# MotorCell_noPow.net
KiCad netlist of a schematic drawn in Altium Designer
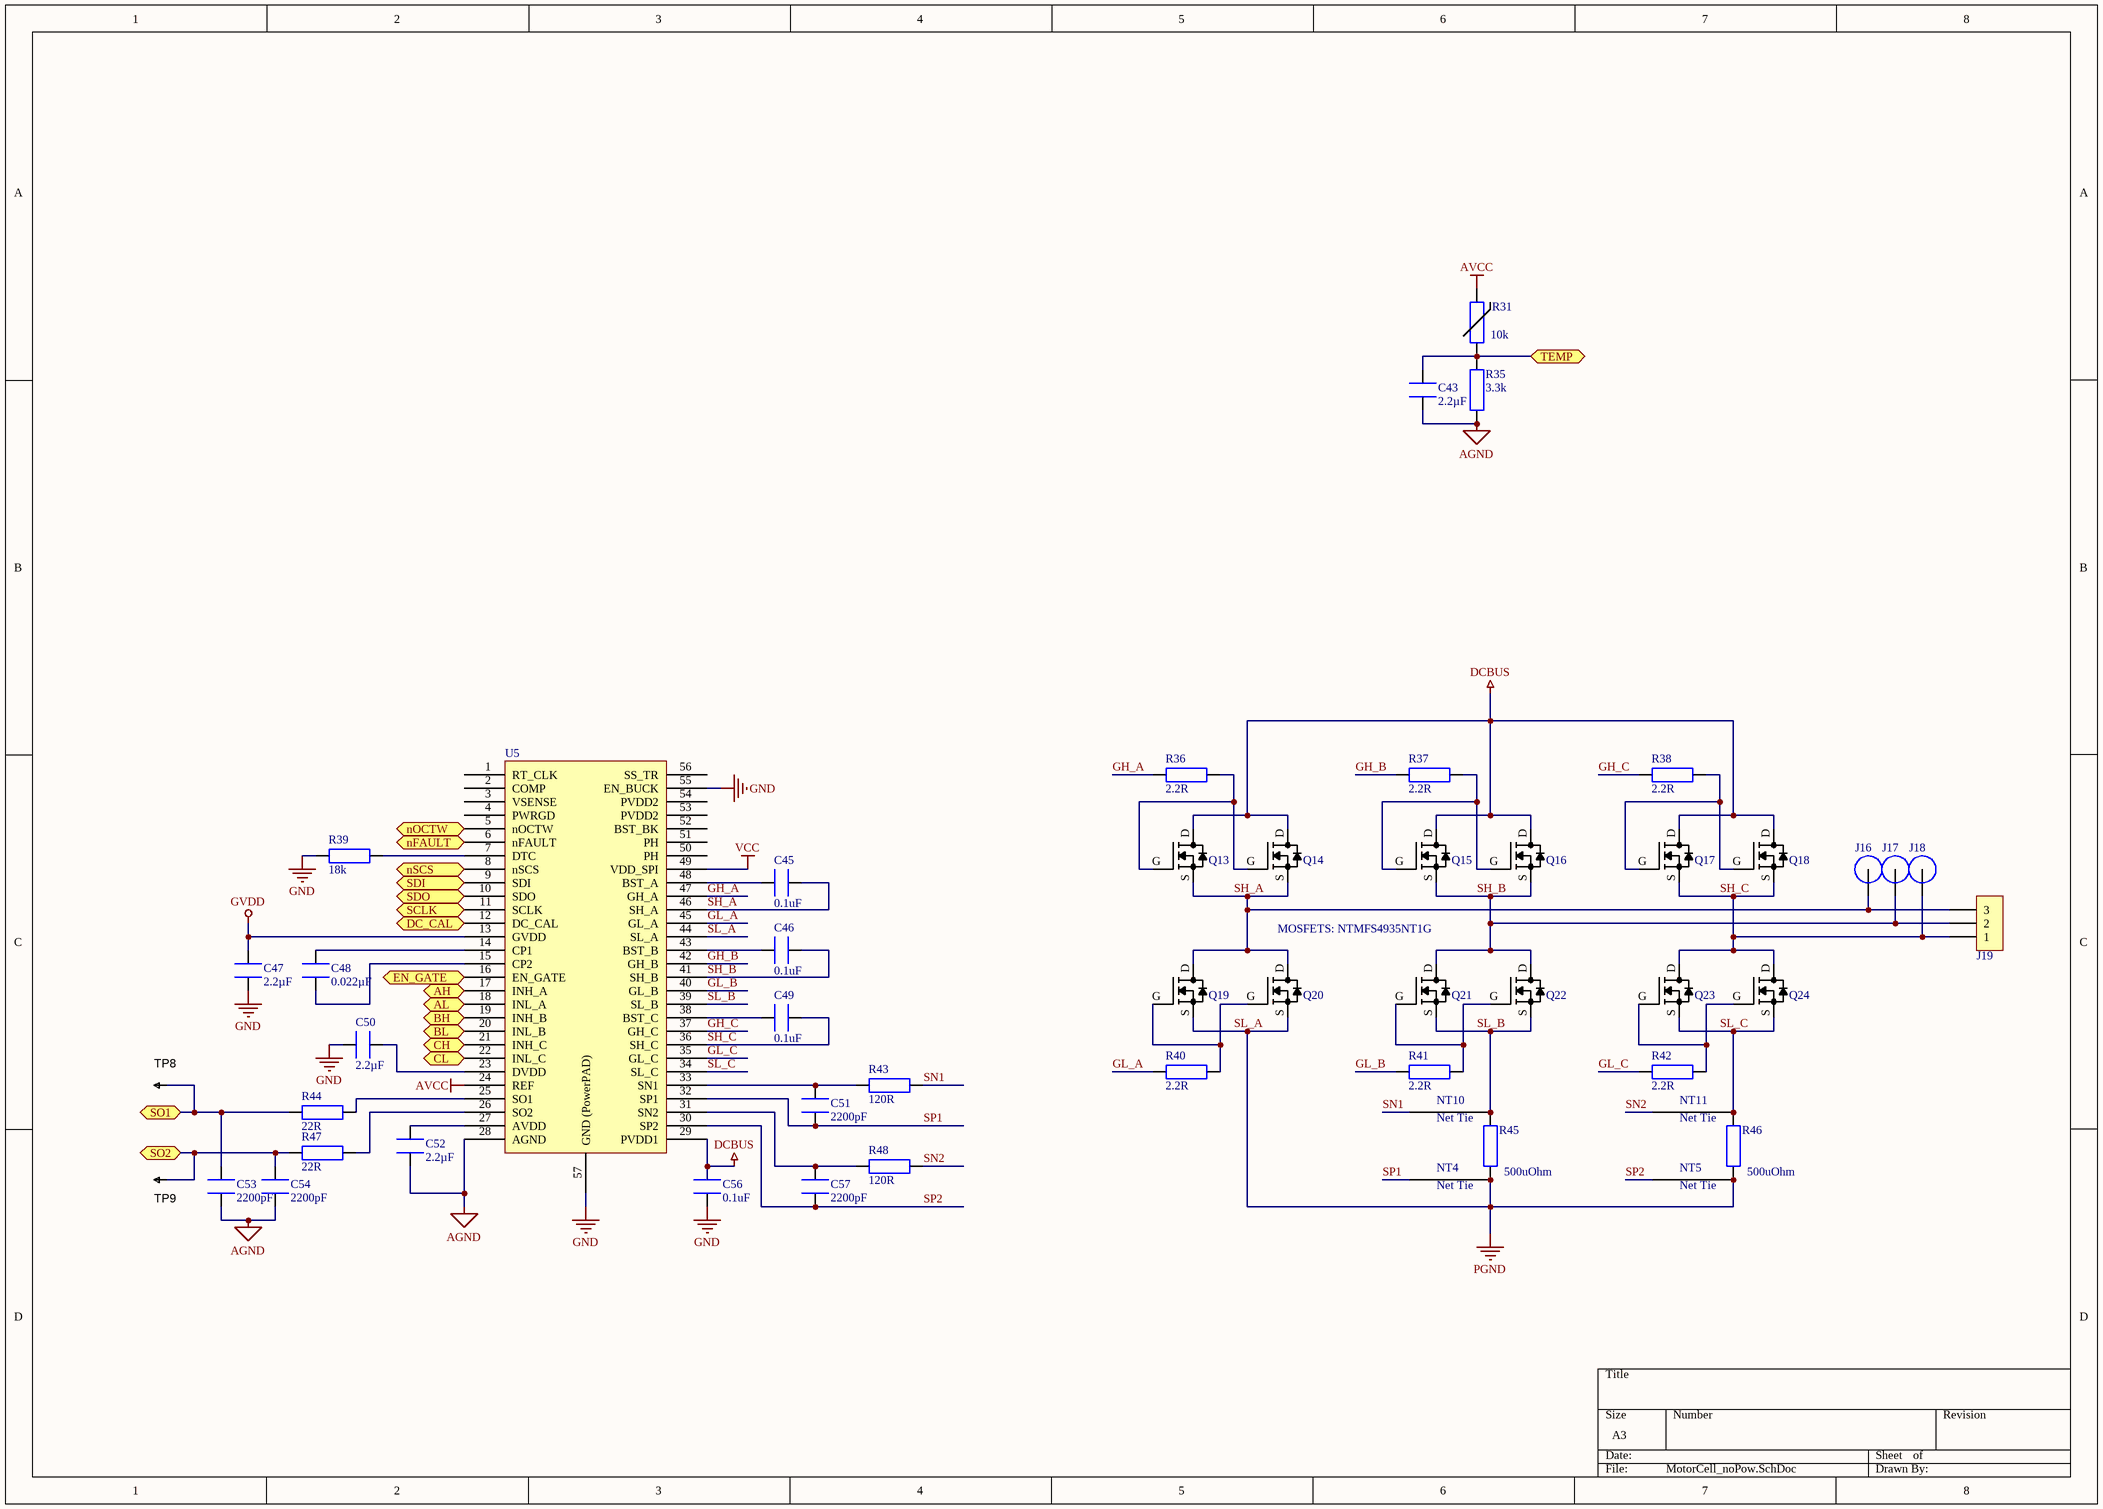
[diagram p0: MotorCell_noPow.SchDoc]

(export (version "E")
  (design (tool "Eeschema 10.0.6"))
  (components
    (comp (ref "C43")
      (value "2.2µF")
      (footprint "CAPC1608X09L")
      (description "CAP CER 2.2UF 16V X5R 0603")
      (fields
        (field (name "MANUFACTURER") "Murata Electronics North America")
        (field (name "MANUFACTURER PART NUMBER") "GRM188R61C225KE15D")
      )
      (libsource (lib "CustomComponents") (part "GRM188R61C225KE15D"))
    )
    (comp (ref "C45")
      (value "0.1uF")
      (footprint "CAPC1608X09L")
      (description "CAP CER 0.1UF 50V X7R 0603")
      (fields
        (field (name "MANUFACTURER") "Murata Electronics North America")
        (field (name "MANUFACTURER PART NUMBER") "GRM188R71H104KA93D")
      )
      (libsource (lib "CustomComponents") (part "GRM188R71H104KA93D"))
    )
    (comp (ref "C46")
      (value "0.1uF")
      (footprint "CAPC1608X09L")
      (description "CAP CER 0.1UF 50V X7R 0603")
      (fields
        (field (name "MANUFACTURER") "Murata Electronics North America")
        (field (name "MANUFACTURER PART NUMBER") "GRM188R71H104KA93D")
      )
      (libsource (lib "CustomComponents") (part "GRM188R71H104KA93D"))
    )
    (comp (ref "C47")
      (value "2.2µF")
      (footprint "CAPC1608X09L")
      (description "CAP CER 2.2UF 16V X5R 0603")
      (fields
        (field (name "MANUFACTURER") "Murata Electronics North America")
        (field (name "MANUFACTURER PART NUMBER") "GRM188R61C225KE15D")
      )
      (libsource (lib "CustomComponents") (part "GRM188R61C225KE15D"))
    )
    (comp (ref "C48")
      (value "0.022µF")
      (footprint "CAPC1608X09L")
      (description "CAP CER 0.022UF 50V X7R 0603")
      (fields
        (field (name "MANUFACTURER") "Murata Electronics North America")
        (field (name "MANUFACTURER PART NUMBER") "GRM188R71H223KA01D")
      )
      (libsource (lib "CustomComponents") (part "GRM188R71H223KA01D"))
    )
    (comp (ref "C49")
      (value "0.1uF")
      (footprint "CAPC1608X09L")
      (description "CAP CER 0.1UF 50V X7R 0603")
      (fields
        (field (name "MANUFACTURER") "Murata Electronics North America")
        (field (name "MANUFACTURER PART NUMBER") "GRM188R71H104KA93D")
      )
      (libsource (lib "CustomComponents") (part "GRM188R71H104KA93D"))
    )
    (comp (ref "C50")
      (value "2.2µF")
      (footprint "CAPC1608X09L")
      (description "CAP CER 2.2UF 16V X5R 0603")
      (fields
        (field (name "MANUFACTURER") "Murata Electronics North America")
        (field (name "MANUFACTURER PART NUMBER") "GRM188R61C225KE15D")
      )
      (libsource (lib "CustomComponents") (part "GRM188R61C225KE15D"))
    )
    (comp (ref "C51")
      (value "2200pF")
      (footprint "CAPC1608X09L")
      (description "CAP CER 2200PF 50V NP0 0603")
      (fields
        (field (name "MANUFACTURER") "Murata Electronics North America")
        (field (name "TOLERANCE") "±5%")
      )
      (libsource (lib "CustomComponents") (part "GRM1885C1H222JA01D"))
    )
    (comp (ref "C52")
      (value "2.2µF")
      (footprint "CAPC1608X09L")
      (description "CAP CER 2.2UF 16V X5R 0603")
      (fields
        (field (name "MANUFACTURER") "Murata Electronics North America")
        (field (name "MANUFACTURER PART NUMBER") "GRM188R61C225KE15D")
      )
      (libsource (lib "CustomComponents") (part "GRM188R61C225KE15D"))
    )
    (comp (ref "C53")
      (value "2200pF")
      (footprint "CAPC1608X09L")
      (description "CAP CER 2200PF 50V NP0 0603")
      (fields
        (field (name "MANUFACTURER") "Murata Electronics North America")
        (field (name "TOLERANCE") "±5%")
      )
      (libsource (lib "CustomComponents") (part "GRM1885C1H222JA01D"))
    )
    (comp (ref "C54")
      (value "2200pF")
      (footprint "CAPC1608X09L")
      (description "CAP CER 2200PF 50V NP0 0603")
      (fields
        (field (name "MANUFACTURER") "Murata Electronics North America")
        (field (name "TOLERANCE") "±5%")
      )
      (libsource (lib "CustomComponents") (part "GRM1885C1H222JA01D"))
    )
    (comp (ref "C56")
      (value "0.1uF")
      (footprint "CAPC1608X09L")
      (description "CAP CER 0.1UF 50V X7R 0603")
      (fields
        (field (name "MANUFACTURER") "Murata Electronics North America")
        (field (name "MANUFACTURER PART NUMBER") "GRM188R71H104KA93D")
      )
      (libsource (lib "CustomComponents") (part "GRM188R71H104KA93D"))
    )
    (comp (ref "C57")
      (value "2200pF")
      (footprint "CAPC1608X09L")
      (description "CAP CER 2200PF 50V NP0 0603")
      (fields
        (field (name "MANUFACTURER") "Murata Electronics North America")
        (field (name "TOLERANCE") "±5%")
      )
      (libsource (lib "CustomComponents") (part "GRM1885C1H222JA01D"))
    )
    (comp (ref "J16")
      (value "~")
      (footprint "M3 Spade Hole")
      (description "M3 Spade Terminal")
      (libsource (lib "CustomComponents") (part "M3 Spade Terminal"))
    )
    (comp (ref "J17")
      (value "~")
      (footprint "M3 Spade Hole")
      (description "M3 Spade Terminal")
      (libsource (lib "CustomComponents") (part "M3 Spade Terminal"))
    )
    (comp (ref "J18")
      (value "~")
      (footprint "M3 Spade Hole")
      (description "M3 Spade Terminal")
      (libsource (lib "CustomComponents") (part "M3 Spade Terminal"))
    )
    (comp (ref "J19")
      (value "1704936")
      (footprint "1704936")
      (description "CONN TERM BLOCK 3POS 7.62MM")
      (fields (field (name "MANUFACTURER") "Phoenix Contact") (field (name "VOLTAGE") "300V"))
      (libsource (lib "CustomComponents") (part "1704936"))
    )
    (comp (ref "NT4")
      (value "0.25mm")
      (footprint "NetTie_0.25mm")
      (libsource (lib "CustomComponents") (part "NetTie_0.25mm"))
    )
    (comp (ref "NT5")
      (value "0.25mm")
      (footprint "NetTie_0.25mm")
      (libsource (lib "CustomComponents") (part "NetTie_0.25mm"))
    )
    (comp (ref "NT10")
      (value "0.25mm")
      (footprint "NetTie_0.25mm")
      (libsource (lib "CustomComponents") (part "NetTie_0.25mm"))
    )
    (comp (ref "NT11")
      (value "0.25mm")
      (footprint "NetTie_0.25mm")
      (libsource (lib "CustomComponents") (part "NetTie_0.25mm"))
    )
    (comp (ref "Q13")
      (value "~")
      (footprint "SO8FL")
      (description "MOSFET N-CH 30V 13A SO8FL")
      (fields
        (field (name "MANUFACTURER") "ON Semiconductor")
        (field (name "MANUFACTURER PART NUMBER") "NTMFS4935NT1G")
      )
      (libsource (lib "CustomComponents") (part "NTMFS4935NT1G"))
    )
    (comp (ref "Q14")
      (value "FILL_FOOTPRINT")
      (footprint "SO8FL_FILL")
      (description "MOSFET N-CH 30V 13A SO8FL")
      (fields
        (field (name "MANUFACTURER") "ON Semiconductor")
        (field (name "MANUFACTURER PART NUMBER") "NTMFS4935NT1G")
      )
      (libsource (lib "CustomComponents") (part "NTMFS4935NT1G"))
    )
    (comp (ref "Q15")
      (value "~")
      (footprint "SO8FL")
      (description "MOSFET N-CH 30V 13A SO8FL")
      (fields
        (field (name "MANUFACTURER") "ON Semiconductor")
        (field (name "MANUFACTURER PART NUMBER") "NTMFS4935NT1G")
      )
      (libsource (lib "CustomComponents") (part "NTMFS4935NT1G"))
    )
    (comp (ref "Q16")
      (value "FILL_FOOTPRINT")
      (footprint "SO8FL_FILL")
      (description "MOSFET N-CH 30V 13A SO8FL")
      (fields
        (field (name "MANUFACTURER") "ON Semiconductor")
        (field (name "MANUFACTURER PART NUMBER") "NTMFS4935NT1G")
      )
      (libsource (lib "CustomComponents") (part "NTMFS4935NT1G"))
    )
    (comp (ref "Q17")
      (value "~")
      (footprint "SO8FL")
      (description "MOSFET N-CH 30V 13A SO8FL")
      (fields
        (field (name "MANUFACTURER") "ON Semiconductor")
        (field (name "MANUFACTURER PART NUMBER") "NTMFS4935NT1G")
      )
      (libsource (lib "CustomComponents") (part "NTMFS4935NT1G"))
    )
    (comp (ref "Q18")
      (value "FILL_FOOTPRINT")
      (footprint "SO8FL_FILL")
      (description "MOSFET N-CH 30V 13A SO8FL")
      (fields
        (field (name "MANUFACTURER") "ON Semiconductor")
        (field (name "MANUFACTURER PART NUMBER") "NTMFS4935NT1G")
      )
      (libsource (lib "CustomComponents") (part "NTMFS4935NT1G"))
    )
    (comp (ref "Q19")
      (value "~")
      (footprint "SO8FL")
      (description "MOSFET N-CH 30V 13A SO8FL")
      (fields
        (field (name "MANUFACTURER") "ON Semiconductor")
        (field (name "MANUFACTURER PART NUMBER") "NTMFS4935NT1G")
      )
      (libsource (lib "CustomComponents") (part "NTMFS4935NT1G"))
    )
    (comp (ref "Q20")
      (value "~")
      (footprint "SO8FL")
      (description "MOSFET N-CH 30V 13A SO8FL")
      (fields
        (field (name "MANUFACTURER") "ON Semiconductor")
        (field (name "MANUFACTURER PART NUMBER") "NTMFS4935NT1G")
      )
      (libsource (lib "CustomComponents") (part "NTMFS4935NT1G"))
    )
    (comp (ref "Q21")
      (value "~")
      (footprint "SO8FL")
      (description "MOSFET N-CH 30V 13A SO8FL")
      (fields
        (field (name "MANUFACTURER") "ON Semiconductor")
        (field (name "MANUFACTURER PART NUMBER") "NTMFS4935NT1G")
      )
      (libsource (lib "CustomComponents") (part "NTMFS4935NT1G"))
    )
    (comp (ref "Q22")
      (value "~")
      (footprint "SO8FL")
      (description "MOSFET N-CH 30V 13A SO8FL")
      (fields
        (field (name "MANUFACTURER") "ON Semiconductor")
        (field (name "MANUFACTURER PART NUMBER") "NTMFS4935NT1G")
      )
      (libsource (lib "CustomComponents") (part "NTMFS4935NT1G"))
    )
    (comp (ref "Q23")
      (value "~")
      (footprint "SO8FL")
      (description "MOSFET N-CH 30V 13A SO8FL")
      (fields
        (field (name "MANUFACTURER") "ON Semiconductor")
        (field (name "MANUFACTURER PART NUMBER") "NTMFS4935NT1G")
      )
      (libsource (lib "CustomComponents") (part "NTMFS4935NT1G"))
    )
    (comp (ref "Q24")
      (value "~")
      (footprint "SO8FL")
      (description "MOSFET N-CH 30V 13A SO8FL")
      (fields
        (field (name "MANUFACTURER") "ON Semiconductor")
        (field (name "MANUFACTURER PART NUMBER") "NTMFS4935NT1G")
      )
      (libsource (lib "CustomComponents") (part "NTMFS4935NT1G"))
    )
    (comp (ref "R31")
      (value "10k")
      (footprint "RESC1005X40N")
      (description "THERMISTOR 10K OHM NTC 0402 SMD")
      (libsource (lib "CustomComponents") (part "NCP15XH103F03RC"))
    )
    (comp (ref "R35")
      (value "3.3k")
      (footprint "RESC1608X55N")
      (description "RES SMD 3.3K OHM 1% 1/10W 0603")
      (fields
        (field (name "MANUFACTURER") "Yageo")
        (field (name "MANUFACTURER PART NUMBER") "RC0603FR-073K3L")
      )
      (libsource (lib "CustomComponents") (part "RC0603FR-073K3L"))
    )
    (comp (ref "R36")
      (value "2.2R")
      (footprint "RESC1608X55N")
      (description "RES SMD 2.2 OHM 1% 1/10W 0603")
      (fields
        (field (name "MANUFACTURER") "Yageo")
        (field (name "MANUFACTURER PART NUMBER") "RC0603FR-072R2L")
      )
      (libsource (lib "CustomComponents") (part "RC0603FR-072R2L"))
    )
    (comp (ref "R37")
      (value "2.2R")
      (footprint "RESC1608X55N")
      (description "RES SMD 2.2 OHM 1% 1/10W 0603")
      (fields
        (field (name "MANUFACTURER") "Yageo")
        (field (name "MANUFACTURER PART NUMBER") "RC0603FR-072R2L")
      )
      (libsource (lib "CustomComponents") (part "RC0603FR-072R2L"))
    )
    (comp (ref "R38")
      (value "2.2R")
      (footprint "RESC1608X55N")
      (description "RES SMD 2.2 OHM 1% 1/10W 0603")
      (fields
        (field (name "MANUFACTURER") "Yageo")
        (field (name "MANUFACTURER PART NUMBER") "RC0603FR-072R2L")
      )
      (libsource (lib "CustomComponents") (part "RC0603FR-072R2L"))
    )
    (comp (ref "R39")
      (value "18k")
      (footprint "RESC1608X55N")
      (description "RES SMD 18K OHM 1% 1/10W 0603")
      (fields
        (field (name "MANUFACTURER") "Yageo")
        (field (name "MANUFACTURER PART NUMBER") "RC0603FR-0718KL")
      )
      (libsource (lib "CustomComponents") (part "RC0603FR-0718KL"))
    )
    (comp (ref "R40")
      (value "2.2R")
      (footprint "RESC1608X55N")
      (description "RES SMD 2.2 OHM 1% 1/10W 0603")
      (fields
        (field (name "MANUFACTURER") "Yageo")
        (field (name "MANUFACTURER PART NUMBER") "RC0603FR-072R2L")
      )
      (libsource (lib "CustomComponents") (part "RC0603FR-072R2L"))
    )
    (comp (ref "R41")
      (value "2.2R")
      (footprint "RESC1608X55N")
      (description "RES SMD 2.2 OHM 1% 1/10W 0603")
      (fields
        (field (name "MANUFACTURER") "Yageo")
        (field (name "MANUFACTURER PART NUMBER") "RC0603FR-072R2L")
      )
      (libsource (lib "CustomComponents") (part "RC0603FR-072R2L"))
    )
    (comp (ref "R42")
      (value "2.2R")
      (footprint "RESC1608X55N")
      (description "RES SMD 2.2 OHM 1% 1/10W 0603")
      (fields
        (field (name "MANUFACTURER") "Yageo")
        (field (name "MANUFACTURER PART NUMBER") "RC0603FR-072R2L")
      )
      (libsource (lib "CustomComponents") (part "RC0603FR-072R2L"))
    )
    (comp (ref "R43")
      (value "120R")
      (footprint "RESC1608X55N")
      (description "RES SMD 120 OHM 1% 1/10W 0603")
      (fields
        (field (name "MANUFACTURER") "Yageo")
        (field (name "MANUFACTURER PART NUMBER") "RC0603FR-07120RL")
      )
      (libsource (lib "CustomComponents") (part "RC0603FR-07120RL"))
    )
    (comp (ref "R44")
      (value "22R")
      (footprint "RESC1608X55N")
      (description "RES SMD 22 OHM 1% 1/10W 0603")
      (fields
        (field (name "MANUFACTURER") "Yageo")
        (field (name "MANUFACTURER PART NUMBER") "RC0603FR-0722RL")
      )
      (libsource (lib "CustomComponents") (part "RC0603FR-0722RL"))
    )
    (comp (ref "R45")
      (value "500uOhm")
      (footprint "RESC6432X09N")
      (description "RES SMD 0.0005 OHM 1% 3W 2512")
      (fields (field (name "MANUFACTURER") "Riedon") (field (name "TOLERANCE") "±1%"))
      (libsource (lib "CustomComponents") (part "CSR2512C0R0005F"))
    )
    (comp (ref "R46")
      (value "500uOhm")
      (footprint "RESC6432X09N")
      (description "RES SMD 0.0005 OHM 1% 3W 2512")
      (fields (field (name "MANUFACTURER") "Riedon") (field (name "TOLERANCE") "±1%"))
      (libsource (lib "CustomComponents") (part "CSR2512C0R0005F"))
    )
    (comp (ref "R47")
      (value "22R")
      (footprint "RESC1608X55N")
      (description "RES SMD 22 OHM 1% 1/10W 0603")
      (fields
        (field (name "MANUFACTURER") "Yageo")
        (field (name "MANUFACTURER PART NUMBER") "RC0603FR-0722RL")
      )
      (libsource (lib "CustomComponents") (part "RC0603FR-0722RL"))
    )
    (comp (ref "R48")
      (value "120R")
      (footprint "RESC1608X55N")
      (description "RES SMD 120 OHM 1% 1/10W 0603")
      (fields
        (field (name "MANUFACTURER") "Yageo")
        (field (name "MANUFACTURER PART NUMBER") "RC0603FR-07120RL")
      )
      (libsource (lib "CustomComponents") (part "RC0603FR-07120RL"))
    )
    (comp (ref "TP8")
      (value "TESTPOINT")
      (footprint "TP-R30")
      (description "SMD test pin")
      (libsource (lib "PBL - Test Points") (part "TESTPOINT"))
    )
    (comp (ref "TP9")
      (value "TESTPOINT")
      (footprint "TP-R30")
      (description "SMD test pin")
      (libsource (lib "PBL - Test Points") (part "TESTPOINT"))
    )
    (comp (ref "U5")
      (value "~")
      (footprint "TSSOP50P810X120_HS-57N")
      (description "MOTOR DRIVER, 3PH, 56HTSSOP")
      (libsource (lib "CustomComponents") (part "DRV8301"))
    )
  )
  (nets
    (net (code "1") (name "/AH") (class "Default")
      (node (ref "U5") (pin "17") (pinfunction "INH_A_17") (pintype "passive"))
    )
    (net (code "2") (name "/AL") (class "Default")
      (node (ref "U5") (pin "18") (pinfunction "INL_A_18") (pintype "passive"))
    )
    (net (code "3") (name "/BH") (class "Default")
      (node (ref "U5") (pin "19") (pinfunction "INH_B_19") (pintype "passive"))
    )
    (net (code "4") (name "/BL") (class "Default")
      (node (ref "U5") (pin "20") (pinfunction "INL_B_20") (pintype "passive"))
    )
    (net (code "5") (name "/CH") (class "Default")
      (node (ref "U5") (pin "21") (pinfunction "INH_C_21") (pintype "passive"))
    )
    (net (code "6") (name "/CL") (class "Default")
      (node (ref "U5") (pin "22") (pinfunction "INL_C_22") (pintype "passive"))
    )
    (net (code "7") (name "/DC_CAL") (class "Default")
      (node (ref "U5") (pin "12") (pinfunction "DC_CAL_12") (pintype "passive"))
    )
    (net (code "8") (name "/EN_GATE") (class "Default")
      (node (ref "U5") (pin "16") (pinfunction "EN_GATE_16") (pintype "passive"))
    )
    (net (code "9") (name "/GH_A") (class "Default")
      (node (ref "R36") (pin "1") (pinfunction "0_1") (pintype "passive"))
      (node (ref "U5") (pin "47") (pinfunction "GH_A_47") (pintype "passive"))
    )
    (net (code "10") (name "/GH_B") (class "Default")
      (node (ref "R37") (pin "1") (pinfunction "0_1") (pintype "passive"))
      (node (ref "U5") (pin "42") (pinfunction "GH_B_42") (pintype "passive"))
    )
    (net (code "11") (name "/GH_C") (class "Default")
      (node (ref "R38") (pin "1") (pinfunction "0_1") (pintype "passive"))
      (node (ref "U5") (pin "37") (pinfunction "GH_C_37") (pintype "passive"))
    )
    (net (code "12") (name "/GL_A") (class "Default")
      (node (ref "R40") (pin "1") (pinfunction "0_1") (pintype "passive"))
      (node (ref "U5") (pin "45") (pinfunction "GL_A_45") (pintype "passive"))
    )
    (net (code "13") (name "/GL_B") (class "Default")
      (node (ref "R41") (pin "1") (pinfunction "0_1") (pintype "passive"))
      (node (ref "U5") (pin "40") (pinfunction "GL_B_40") (pintype "passive"))
    )
    (net (code "14") (name "/GL_C") (class "Default")
      (node (ref "R42") (pin "1") (pinfunction "0_1") (pintype "passive"))
      (node (ref "U5") (pin "35") (pinfunction "GL_C_35") (pintype "passive"))
    )
    (net (code "15") (name "/SCLK") (class "Default")
      (node (ref "U5") (pin "11") (pinfunction "SCLK_11") (pintype "passive"))
    )
    (net (code "16") (name "/SDI") (class "Default")
      (node (ref "U5") (pin "9") (pinfunction "SDI_9") (pintype "passive"))
    )
    (net (code "17") (name "/SDO") (class "Default")
      (node (ref "U5") (pin "10") (pinfunction "SDO_10") (pintype "passive"))
    )
    (net (code "18") (name "/SH_A") (class "Default")
      (node (ref "C45") (pin "1") (pinfunction "1_1") (pintype "passive"))
      (node (ref "J16") (pin "1") (pinfunction "1_1") (pintype "passive"))
      (node (ref "J19") (pin "3") (pinfunction "3_3") (pintype "passive"))
      (node (ref "Q13") (pin "S") (pinfunction "S_S") (pintype "passive"))
      (node (ref "Q14") (pin "S") (pinfunction "S_S") (pintype "passive"))
      (node (ref "Q19") (pin "D") (pinfunction "D_D") (pintype "passive"))
      (node (ref "Q20") (pin "D") (pinfunction "D_D") (pintype "passive"))
      (node (ref "U5") (pin "46") (pinfunction "SH_A_46") (pintype "passive"))
    )
    (net (code "19") (name "/SH_B") (class "Default")
      (node (ref "C46") (pin "1") (pinfunction "1_1") (pintype "passive"))
      (node (ref "J17") (pin "1") (pinfunction "1_1") (pintype "passive"))
      (node (ref "J19") (pin "2") (pinfunction "2_2") (pintype "passive"))
      (node (ref "Q15") (pin "S") (pinfunction "S_S") (pintype "passive"))
      (node (ref "Q16") (pin "S") (pinfunction "S_S") (pintype "passive"))
      (node (ref "Q21") (pin "D") (pinfunction "D_D") (pintype "passive"))
      (node (ref "Q22") (pin "D") (pinfunction "D_D") (pintype "passive"))
      (node (ref "U5") (pin "41") (pinfunction "SH_B_41") (pintype "passive"))
    )
    (net (code "20") (name "/SH_C") (class "Default")
      (node (ref "C49") (pin "1") (pinfunction "1_1") (pintype "passive"))
      (node (ref "J18") (pin "1") (pinfunction "1_1") (pintype "passive"))
      (node (ref "J19") (pin "1") (pinfunction "1_1") (pintype "passive"))
      (node (ref "Q17") (pin "S") (pinfunction "S_S") (pintype "passive"))
      (node (ref "Q18") (pin "S") (pinfunction "S_S") (pintype "passive"))
      (node (ref "Q23") (pin "D") (pinfunction "D_D") (pintype "passive"))
      (node (ref "Q24") (pin "D") (pinfunction "D_D") (pintype "passive"))
      (node (ref "U5") (pin "36") (pinfunction "SH_C_36") (pintype "passive"))
    )
    (net (code "21") (name "/SL_B") (class "Default")
      (node (ref "NT10") (pin "2") (pintype "passive"))
      (node (ref "Q21") (pin "S") (pinfunction "S_S") (pintype "passive"))
      (node (ref "Q22") (pin "S") (pinfunction "S_S") (pintype "passive"))
      (node (ref "R45") (pin "2") (pinfunction "0_2") (pintype "passive"))
      (node (ref "U5") (pin "39") (pinfunction "SL_B_39") (pintype "passive"))
    )
    (net (code "22") (name "/SL_C") (class "Default")
      (node (ref "NT11") (pin "2") (pintype "passive"))
      (node (ref "Q23") (pin "S") (pinfunction "S_S") (pintype "passive"))
      (node (ref "Q24") (pin "S") (pinfunction "S_S") (pintype "passive"))
      (node (ref "R46") (pin "2") (pinfunction "0_2") (pintype "passive"))
      (node (ref "U5") (pin "34") (pinfunction "SL_C_34") (pintype "passive"))
    )
    (net (code "23") (name "/SN1") (class "Default")
      (node (ref "NT10") (pin "1") (pintype "passive"))
      (node (ref "R43") (pin "1") (pinfunction "0_1") (pintype "passive"))
    )
    (net (code "24") (name "/SN2") (class "Default")
      (node (ref "NT11") (pin "1") (pintype "passive"))
      (node (ref "R48") (pin "1") (pinfunction "0_1") (pintype "passive"))
    )
    (net (code "25") (name "/SO1") (class "Default")
      (node (ref "C53") (pin "1") (pinfunction "1_1") (pintype "passive"))
      (node (ref "R44") (pin "2") (pinfunction "0_2") (pintype "passive"))
      (node (ref "TP8") (pin "1") (pintype "passive"))
    )
    (net (code "26") (name "/SO2") (class "Default")
      (node (ref "C54") (pin "1") (pinfunction "1_1") (pintype "passive"))
      (node (ref "R47") (pin "2") (pinfunction "0_2") (pintype "passive"))
      (node (ref "TP9") (pin "1") (pintype "passive"))
    )
    (net (code "27") (name "/SP1") (class "Default")
      (node (ref "C51") (pin "2") (pinfunction "2_2") (pintype "passive"))
      (node (ref "NT4") (pin "1") (pintype "passive"))
      (node (ref "U5") (pin "32") (pinfunction "SP1_32") (pintype "passive"))
    )
    (net (code "28") (name "/SP2") (class "Default")
      (node (ref "C57") (pin "2") (pinfunction "2_2") (pintype "passive"))
      (node (ref "NT5") (pin "1") (pintype "passive"))
      (node (ref "U5") (pin "30") (pinfunction "SP2_30") (pintype "passive"))
    )
    (net (code "29") (name "/TEMP") (class "Default")
      (node (ref "C43") (pin "2") (pinfunction "2_2") (pintype "passive"))
      (node (ref "R31") (pin "1") (pinfunction "0_1") (pintype "passive"))
      (node (ref "R35") (pin "1") (pinfunction "0_1") (pintype "passive"))
    )
    (net (code "30") (name "/nFAULT") (class "Default")
      (node (ref "U5") (pin "6") (pinfunction "nFAULT_6") (pintype "passive"))
    )
    (net (code "31") (name "/nOCTW") (class "Default")
      (node (ref "U5") (pin "5") (pinfunction "nOCTW_5") (pintype "passive"))
    )
    (net (code "32") (name "/nSCS") (class "Default")
      (node (ref "U5") (pin "8") (pinfunction "nSCS_8") (pintype "passive"))
    )
    (net (code "33") (name "AGND") (class "Default")
      (node (ref "C43") (pin "1") (pinfunction "1_1") (pintype "passive"))
      (node (ref "C52") (pin "1") (pinfunction "1_1") (pintype "passive"))
      (node (ref "C53") (pin "2") (pinfunction "2_2") (pintype "passive"))
      (node (ref "C54") (pin "2") (pinfunction "2_2") (pintype "passive"))
      (node (ref "R35") (pin "2") (pinfunction "0_2") (pintype "passive"))
      (node (ref "U5") (pin "28") (pinfunction "AGND_28") (pintype "passive"))
    )
    (net (code "34") (name "AVCC") (class "Default")
      (node (ref "R31") (pin "2") (pinfunction "0_2") (pintype "passive"))
      (node (ref "U5") (pin "24") (pinfunction "REF_24") (pintype "passive"))
    )
    (net (code "35") (name "DCBUS") (class "Default")
      (node (ref "C56") (pin "1") (pinfunction "1_1") (pintype "passive"))
      (node (ref "Q13") (pin "D") (pinfunction "D_D") (pintype "passive"))
      (node (ref "Q14") (pin "D") (pinfunction "D_D") (pintype "passive"))
      (node (ref "Q15") (pin "D") (pinfunction "D_D") (pintype "passive"))
      (node (ref "Q16") (pin "D") (pinfunction "D_D") (pintype "passive"))
      (node (ref "Q17") (pin "D") (pinfunction "D_D") (pintype "passive"))
      (node (ref "Q18") (pin "D") (pinfunction "D_D") (pintype "passive"))
      (node (ref "U5") (pin "29") (pinfunction "PVDD1_29") (pintype "passive"))
    )
    (net (code "36") (name "GND") (class "Default")
      (node (ref "C47") (pin "1") (pinfunction "1_1") (pintype "passive"))
      (node (ref "C50") (pin "1") (pinfunction "1_1") (pintype "passive"))
      (node (ref "C56") (pin "2") (pinfunction "2_2") (pintype "passive"))
      (node (ref "R39") (pin "2") (pinfunction "0_2") (pintype "passive"))
      (node (ref "U5") (pin "55") (pinfunction "EN_BUCK_55") (pintype "passive"))
      (node (ref "U5") (pin "57") (pinfunction "GND_(PowerPAD)_57") (pintype "passive"))
    )
    (net (code "37") (name "GVDD") (class "Default")
      (node (ref "C47") (pin "2") (pinfunction "2_2") (pintype "passive"))
      (node (ref "U5") (pin "13") (pinfunction "GVDD_13") (pintype "passive"))
    )
    (net (code "38") (name "Net-(Q13-PadG)") (class "Default")
      (node (ref "Q13") (pin "G") (pinfunction "G_G") (pintype "passive"))
      (node (ref "Q14") (pin "G") (pinfunction "G_G") (pintype "passive"))
      (node (ref "R36") (pin "2") (pinfunction "0_2") (pintype "passive"))
    )
    (net (code "39") (name "Net-(Q15-PadG)") (class "Default")
      (node (ref "Q15") (pin "G") (pinfunction "G_G") (pintype "passive"))
      (node (ref "Q16") (pin "G") (pinfunction "G_G") (pintype "passive"))
      (node (ref "R37") (pin "2") (pinfunction "0_2") (pintype "passive"))
    )
    (net (code "40") (name "Net-(Q17-PadG)") (class "Default")
      (node (ref "Q17") (pin "G") (pinfunction "G_G") (pintype "passive"))
      (node (ref "Q18") (pin "G") (pinfunction "G_G") (pintype "passive"))
      (node (ref "R38") (pin "2") (pinfunction "0_2") (pintype "passive"))
    )
    (net (code "41") (name "Net-(Q19-PadG)") (class "Default")
      (node (ref "Q19") (pin "G") (pinfunction "G_G") (pintype "passive"))
      (node (ref "Q20") (pin "G") (pinfunction "G_G") (pintype "passive"))
      (node (ref "R40") (pin "2") (pinfunction "0_2") (pintype "passive"))
    )
    (net (code "42") (name "Net-(Q21-PadG)") (class "Default")
      (node (ref "Q21") (pin "G") (pinfunction "G_G") (pintype "passive"))
      (node (ref "Q22") (pin "G") (pinfunction "G_G") (pintype "passive"))
      (node (ref "R41") (pin "2") (pinfunction "0_2") (pintype "passive"))
    )
    (net (code "43") (name "Net-(Q23-PadG)") (class "Default")
      (node (ref "Q23") (pin "G") (pinfunction "G_G") (pintype "passive"))
      (node (ref "Q24") (pin "G") (pinfunction "G_G") (pintype "passive"))
      (node (ref "R42") (pin "2") (pinfunction "0_2") (pintype "passive"))
    )
    (net (code "44") (name "Net-(U5-AVDD)") (class "Default")
      (node (ref "C52") (pin "2") (pinfunction "2_2") (pintype "passive"))
      (node (ref "U5") (pin "27") (pinfunction "AVDD_27") (pintype "passive"))
    )
    (net (code "45") (name "Net-(U5-BST_A)") (class "Default")
      (node (ref "C45") (pin "2") (pinfunction "2_2") (pintype "passive"))
      (node (ref "U5") (pin "48") (pinfunction "BST_A_48") (pintype "passive"))
    )
    (net (code "46") (name "Net-(U5-BST_B)") (class "Default")
      (node (ref "C46") (pin "2") (pinfunction "2_2") (pintype "passive"))
      (node (ref "U5") (pin "43") (pinfunction "BST_B_43") (pintype "passive"))
    )
    (net (code "47") (name "Net-(U5-BST_C)") (class "Default")
      (node (ref "C49") (pin "2") (pinfunction "2_2") (pintype "passive"))
      (node (ref "U5") (pin "38") (pinfunction "BST_C_38") (pintype "passive"))
    )
    (net (code "48") (name "Net-(U5-CP1)") (class "Default")
      (node (ref "C48") (pin "1") (pinfunction "1_1") (pintype "passive"))
      (node (ref "U5") (pin "14") (pinfunction "CP1_14") (pintype "passive"))
    )
    (net (code "49") (name "Net-(U5-CP2)") (class "Default")
      (node (ref "C48") (pin "2") (pinfunction "2_2") (pintype "passive"))
      (node (ref "U5") (pin "15") (pinfunction "CP2_15") (pintype "passive"))
    )
    (net (code "50") (name "Net-(U5-DTC)") (class "Default")
      (node (ref "R39") (pin "1") (pinfunction "0_1") (pintype "passive"))
      (node (ref "U5") (pin "7") (pinfunction "DTC_7") (pintype "passive"))
    )
    (net (code "51") (name "Net-(U5-DVDD)") (class "Default")
      (node (ref "C50") (pin "2") (pinfunction "2_2") (pintype "passive"))
      (node (ref "U5") (pin "23") (pinfunction "DVDD_23") (pintype "passive"))
    )
    (net (code "52") (name "Net-(U5-SN1)") (class "Default")
      (node (ref "C51") (pin "1") (pinfunction "1_1") (pintype "passive"))
      (node (ref "R43") (pin "2") (pinfunction "0_2") (pintype "passive"))
      (node (ref "U5") (pin "33") (pinfunction "SN1_33") (pintype "passive"))
    )
    (net (code "53") (name "Net-(U5-SN2)") (class "Default")
      (node (ref "C57") (pin "1") (pinfunction "1_1") (pintype "passive"))
      (node (ref "R48") (pin "2") (pinfunction "0_2") (pintype "passive"))
      (node (ref "U5") (pin "31") (pinfunction "SN2_31") (pintype "passive"))
    )
    (net (code "54") (name "Net-(U5-SO1)") (class "Default")
      (node (ref "R44") (pin "1") (pinfunction "0_1") (pintype "passive"))
      (node (ref "U5") (pin "25") (pinfunction "SO1_25") (pintype "passive"))
    )
    (net (code "55") (name "Net-(U5-SO2)") (class "Default")
      (node (ref "R47") (pin "1") (pinfunction "0_1") (pintype "passive"))
      (node (ref "U5") (pin "26") (pinfunction "SO2_26") (pintype "passive"))
    )
    (net (code "56") (name "PGND") (class "Default")
      (node (ref "NT4") (pin "2") (pintype "passive"))
      (node (ref "NT5") (pin "2") (pintype "passive"))
      (node (ref "Q19") (pin "S") (pinfunction "S_S") (pintype "passive"))
      (node (ref "Q20") (pin "S") (pinfunction "S_S") (pintype "passive"))
      (node (ref "R45") (pin "1") (pinfunction "0_1") (pintype "passive"))
      (node (ref "R46") (pin "1") (pinfunction "0_1") (pintype "passive"))
      (node (ref "U5") (pin "44") (pinfunction "SL_A_44") (pintype "passive"))
    )
    (net (code "57") (name "VCC") (class "Default")
      (node (ref "U5") (pin "49") (pinfunction "VDD_SPI_49") (pintype "passive"))
    )
    (net (code "58") (name "unconnected-(U5-BST_BK-Pad52)") (class "Default")
      (node (ref "U5") (pin "52") (pinfunction "BST_BK_52") (pintype "passive"))
    )
    (net (code "59") (name "unconnected-(U5-COMP-Pad2)") (class "Default")
      (node (ref "U5") (pin "2") (pinfunction "COMP_2") (pintype "passive"))
    )
    (net (code "60") (name "unconnected-(U5-PH-Pad50)") (class "Default")
      (node (ref "U5") (pin "50") (pinfunction "PH_50") (pintype "passive"))
    )
    (net (code "61") (name "unconnected-(U5-PH-Pad51)") (class "Default")
      (node (ref "U5") (pin "51") (pinfunction "PH_51") (pintype "passive"))
    )
    (net (code "62") (name "unconnected-(U5-PVDD2-Pad53)") (class "Default")
      (node (ref "U5") (pin "53") (pinfunction "PVDD2_53") (pintype "passive"))
    )
    (net (code "63") (name "unconnected-(U5-PVDD2-Pad54)") (class "Default")
      (node (ref "U5") (pin "54") (pinfunction "PVDD2_54") (pintype "passive"))
    )
    (net (code "64") (name "unconnected-(U5-PWRGD-Pad4)") (class "Default")
      (node (ref "U5") (pin "4") (pinfunction "PWRGD_4") (pintype "passive"))
    )
    (net (code "65") (name "unconnected-(U5-RT_CLK-Pad1)") (class "Default")
      (node (ref "U5") (pin "1") (pinfunction "RT_CLK_1") (pintype "passive"))
    )
    (net (code "66") (name "unconnected-(U5-SS_TR-Pad56)") (class "Default")
      (node (ref "U5") (pin "56") (pinfunction "SS_TR_56") (pintype "passive"))
    )
    (net (code "67") (name "unconnected-(U5-VSENSE-Pad3)") (class "Default")
      (node (ref "U5") (pin "3") (pinfunction "VSENSE_3") (pintype "passive"))
    )
  )
)
